# mouse.net
KiCad netlist of a schematic drawn in EAGLE
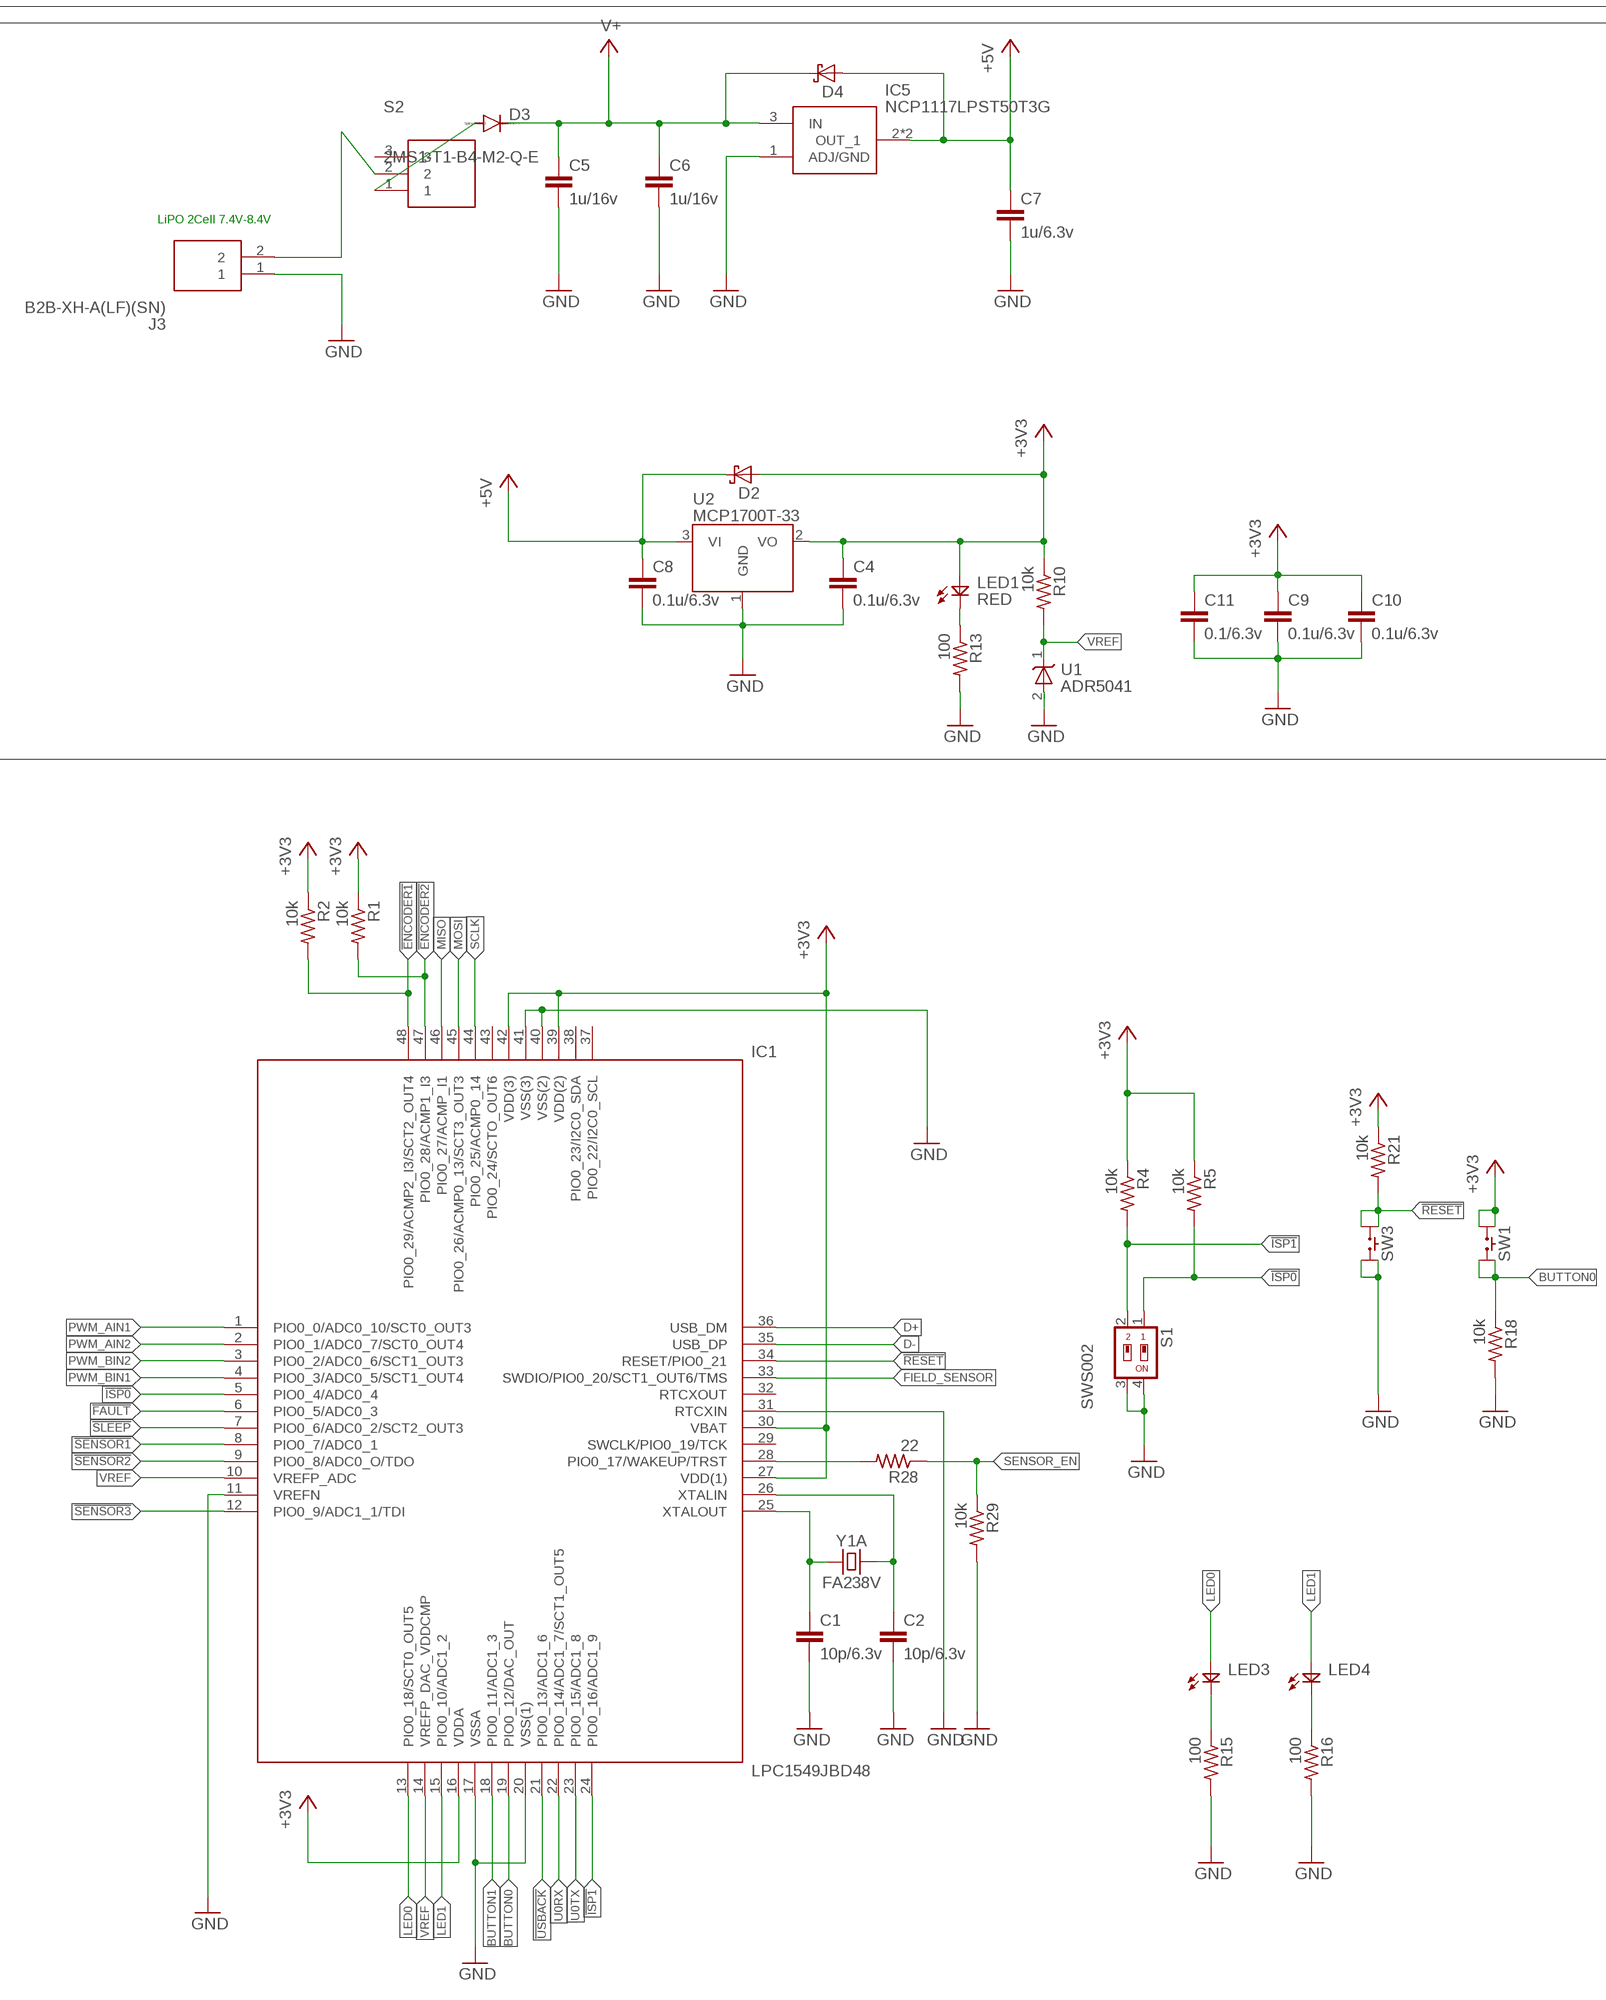
[diagram p0: schematic, sheet 1, part 1 of 2]
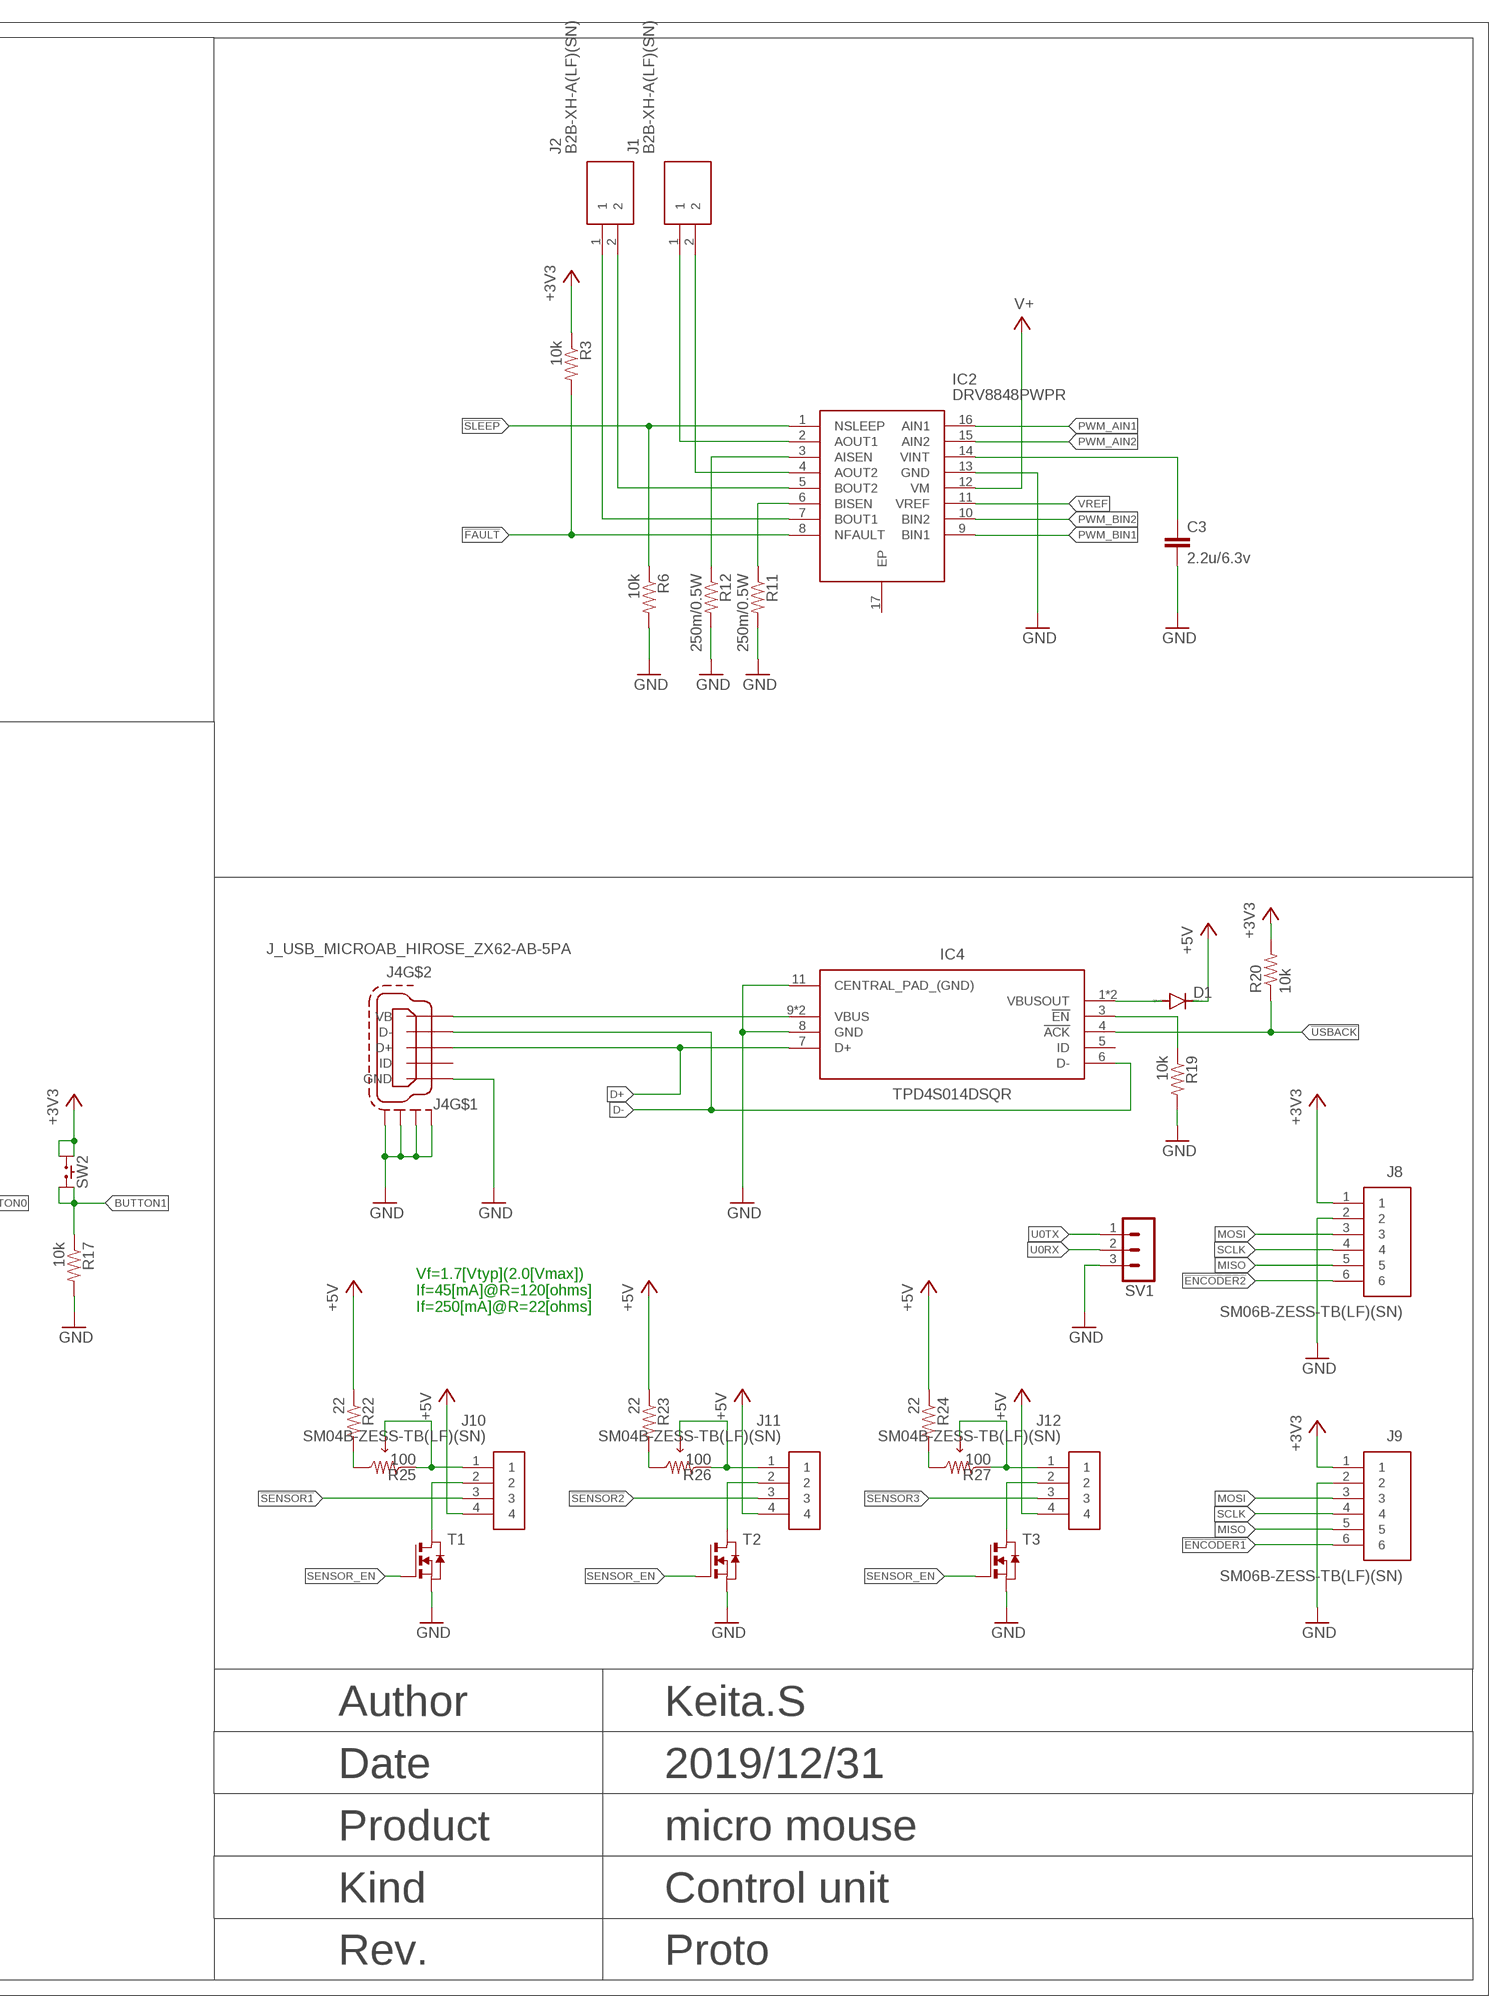
[diagram p1: schematic, sheet 1, part 2 of 2]

(export (version "E")
  (design (tool "Eeschema 10.0.6"))
  (components
    (comp (ref "C1")
      (value "10p/6.3v")
      (footprint "eagle-import:C0603")
      (libsource (lib "eagle-import") (part "C-EUC0603"))
    )
    (comp (ref "C2")
      (value "10p/6.3v")
      (footprint "eagle-import:C0603")
      (libsource (lib "eagle-import") (part "C-EUC0603"))
    )
    (comp (ref "C3")
      (value "2.2u/6.3v")
      (footprint "eagle-import:C0603")
      (libsource (lib "eagle-import") (part "C-EUC0603"))
    )
    (comp (ref "C4")
      (value "0.1u/6.3v")
      (footprint "eagle-import:C0603")
      (libsource (lib "eagle-import") (part "C-EUC0603"))
    )
    (comp (ref "C5")
      (value "1u/16v")
      (footprint "eagle-import:C0603")
      (libsource (lib "eagle-import") (part "C-EUC0603"))
    )
    (comp (ref "C6")
      (value "1u/16v")
      (footprint "eagle-import:C0603")
      (libsource (lib "eagle-import") (part "C-EUC0603"))
    )
    (comp (ref "C7")
      (value "1u/6.3v")
      (footprint "eagle-import:C0603")
      (libsource (lib "eagle-import") (part "C-EUC0603"))
    )
    (comp (ref "C8")
      (value "0.1u/6.3v")
      (footprint "eagle-import:C0603")
      (libsource (lib "eagle-import") (part "C-EUC0603"))
    )
    (comp (ref "C9")
      (value "0.1u/6.3v")
      (footprint "eagle-import:C0603")
      (libsource (lib "eagle-import") (part "C-EUC0603"))
    )
    (comp (ref "C10")
      (value "0.1u/6.3v")
      (footprint "eagle-import:C0603")
      (libsource (lib "eagle-import") (part "C-EUC0603"))
    )
    (comp (ref "C11")
      (value "0.1/6.3v")
      (footprint "eagle-import:C0603")
      (libsource (lib "eagle-import") (part "C-EUC0603"))
    )
    (comp (ref "D1")
      (value "DIODE-SMB")
      (footprint "eagle-import:SMB")
      (libsource (lib "eagle-import") (part "DIODE-SMB"))
    )
    (comp (ref "D2")
      (value "SBD-SOD523")
      (footprint "eagle-import:DIODE_SOD523")
      (libsource (lib "eagle-import") (part "SBD-SOD523"))
    )
    (comp (ref "D3")
      (value "DIODE-SMB")
      (footprint "eagle-import:SMB")
      (libsource (lib "eagle-import") (part "DIODE-SMB"))
    )
    (comp (ref "D4")
      (value "SBD-SOD523")
      (footprint "eagle-import:DIODE_SOD523")
      (libsource (lib "eagle-import") (part "SBD-SOD523"))
    )
    (comp (ref "IC1")
      (value "LPC1549JBD48")
      (footprint "eagle-import:QFP50P900X900X160-48N")
      (libsource (lib "eagle-import") (part "LPC1549JBD48"))
    )
    (comp (ref "IC2")
      (value "DRV8848PWPR")
      (footprint "eagle-import:SOP65P640X120-17N")
      (libsource (lib "eagle-import") (part "DRV8848PWPR"))
    )
    (comp (ref "IC4")
      (value "TPD4S014DSQR")
      (footprint "eagle-import:SON40P200X200X80-11N")
      (fields (field (name "RS_PART_NUMBER") "7422968"))
      (libsource (lib "eagle-import") (part "TPD4S014DSQR"))
    )
    (comp (ref "IC5")
      (value "NCP1117LPST50T3G")
      (footprint "eagle-import:SOT230P700X180-4N")
      (fields (field (name "RS_PART_NUMBER") "7857187P"))
      (libsource (lib "eagle-import") (part "NCP1117LPST50T3G"))
    )
    (comp (ref "J1")
      (value "B2B-XH-A(LF)(SN)")
      (footprint "eagle-import:SHDR2W64P0X250_1X2_740X575X700")
      (fields (field (name "RS_PART_NUMBER") "8201554P"))
      (libsource (lib "eagle-import") (part "B2B-XH-A(LF)(SN)"))
    )
    (comp (ref "J2")
      (value "B2B-XH-A(LF)(SN)")
      (footprint "eagle-import:SHDR2W64P0X250_1X2_740X575X700")
      (fields (field (name "RS_PART_NUMBER") "8201554P"))
      (libsource (lib "eagle-import") (part "B2B-XH-A(LF)(SN)"))
    )
    (comp (ref "J3")
      (value "B2B-XH-A(LF)(SN)")
      (footprint "eagle-import:SHDR2W64P0X250_1X2_740X575X700")
      (fields (field (name "RS_PART_NUMBER") "8201554P"))
      (libsource (lib "eagle-import") (part "B2B-XH-A(LF)(SN)"))
    )
    (comp (ref "J4")
      (value "J_USB_MICROAB_HIROSE_ZX62-AB-5PA")
      (footprint "eagle-import:J_USB_MICROAB_HIROSE_ZX62-AB-5PA")
      (libsource (lib "eagle-import") (part "J_USB_MICROAB_HIROSE_ZX62-AB-5PA"))
    )
    (comp (ref "J8")
      (value "SM06B-ZESS-TB(LF)(SN)")
      (footprint "eagle-import:SM06BZESSTBLFSN")
      (libsource (lib "eagle-import") (part "SM06B-ZESS-TB(LF)(SN)"))
    )
    (comp (ref "J9")
      (value "SM06B-ZESS-TB(LF)(SN)")
      (footprint "eagle-import:SM06BZESSTBLFSN")
      (libsource (lib "eagle-import") (part "SM06B-ZESS-TB(LF)(SN)"))
    )
    (comp (ref "J10")
      (value "SM04B-ZESS-TB(LF)(SN)")
      (footprint "eagle-import:SM04BZESSTBLFSN")
      (libsource (lib "eagle-import") (part "SM04B-ZESS-TB(LF)(SN)"))
    )
    (comp (ref "J11")
      (value "SM04B-ZESS-TB(LF)(SN)")
      (footprint "eagle-import:SM04BZESSTBLFSN")
      (libsource (lib "eagle-import") (part "SM04B-ZESS-TB(LF)(SN)"))
    )
    (comp (ref "J12")
      (value "SM04B-ZESS-TB(LF)(SN)")
      (footprint "eagle-import:SM04BZESSTBLFSN")
      (libsource (lib "eagle-import") (part "SM04B-ZESS-TB(LF)(SN)"))
    )
    (comp (ref "LED1")
      (value "RED")
      (footprint "eagle-import:LED1608")
      (libsource (lib "eagle-import") (part "LED1608"))
    )
    (comp (ref "LED3")
      (value "LED1608")
      (footprint "eagle-import:LED1608")
      (libsource (lib "eagle-import") (part "LED1608"))
    )
    (comp (ref "LED4")
      (value "LED1608")
      (footprint "eagle-import:LED1608")
      (libsource (lib "eagle-import") (part "LED1608"))
    )
    (comp (ref "R1")
      (value "10k")
      (footprint "eagle-import:R0603")
      (libsource (lib "eagle-import") (part "R-US_R0603"))
    )
    (comp (ref "R2")
      (value "10k")
      (footprint "eagle-import:R0603")
      (libsource (lib "eagle-import") (part "R-US_R0603"))
    )
    (comp (ref "R3")
      (value "10k")
      (footprint "eagle-import:R0603")
      (libsource (lib "eagle-import") (part "R-US_R0603"))
    )
    (comp (ref "R4")
      (value "10k")
      (footprint "eagle-import:R0603")
      (libsource (lib "eagle-import") (part "R-US_R0603"))
    )
    (comp (ref "R5")
      (value "10k")
      (footprint "eagle-import:R0603")
      (libsource (lib "eagle-import") (part "R-US_R0603"))
    )
    (comp (ref "R6")
      (value "10k")
      (footprint "eagle-import:R0603")
      (libsource (lib "eagle-import") (part "R-US_R0603"))
    )
    (comp (ref "R10")
      (value "10k")
      (footprint "eagle-import:R0603")
      (libsource (lib "eagle-import") (part "R-US_R0603"))
    )
    (comp (ref "R11")
      (value "250m/0.5W")
      (footprint "eagle-import:R1206")
      (libsource (lib "eagle-import") (part "R-US_R1206"))
    )
    (comp (ref "R12")
      (value "250m/0.5W")
      (footprint "eagle-import:R1206")
      (libsource (lib "eagle-import") (part "R-US_R1206"))
    )
    (comp (ref "R13")
      (value "100")
      (footprint "eagle-import:R0603")
      (libsource (lib "eagle-import") (part "R-US_R0603"))
    )
    (comp (ref "R15")
      (value "100")
      (footprint "eagle-import:R0603")
      (libsource (lib "eagle-import") (part "R-US_R0603"))
    )
    (comp (ref "R16")
      (value "100")
      (footprint "eagle-import:R0603")
      (libsource (lib "eagle-import") (part "R-US_R0603"))
    )
    (comp (ref "R17")
      (value "10k")
      (footprint "eagle-import:R0603")
      (libsource (lib "eagle-import") (part "R-US_R0603"))
    )
    (comp (ref "R18")
      (value "10k")
      (footprint "eagle-import:R0603")
      (libsource (lib "eagle-import") (part "R-US_R0603"))
    )
    (comp (ref "R19")
      (value "10k")
      (footprint "eagle-import:R0603")
      (libsource (lib "eagle-import") (part "R-US_R0603"))
    )
    (comp (ref "R20")
      (value "10k")
      (footprint "eagle-import:R0603")
      (libsource (lib "eagle-import") (part "R-US_R0603"))
    )
    (comp (ref "R21")
      (value "10k")
      (footprint "eagle-import:R0603")
      (libsource (lib "eagle-import") (part "R-US_R0603"))
    )
    (comp (ref "R22")
      (value "22")
      (footprint "eagle-import:R0603")
      (libsource (lib "eagle-import") (part "R-US_R0603"))
    )
    (comp (ref "R23")
      (value "22")
      (footprint "eagle-import:R0603")
      (libsource (lib "eagle-import") (part "R-US_R0603"))
    )
    (comp (ref "R24")
      (value "22")
      (footprint "eagle-import:R0603")
      (libsource (lib "eagle-import") (part "R-US_R0603"))
    )
    (comp (ref "R25")
      (value "100")
      (footprint "eagle-import:CT6EP203")
      (fields (field (name "MANUFACTURER_PART_NUMBER") "CT6EP203"))
      (libsource (lib "eagle-import") (part "CT6EP203"))
    )
    (comp (ref "R26")
      (value "100")
      (footprint "eagle-import:CT6EP203")
      (fields (field (name "MANUFACTURER_PART_NUMBER") "CT6EP203"))
      (libsource (lib "eagle-import") (part "CT6EP203"))
    )
    (comp (ref "R27")
      (value "100")
      (footprint "eagle-import:CT6EP203")
      (fields (field (name "MANUFACTURER_PART_NUMBER") "CT6EP203"))
      (libsource (lib "eagle-import") (part "CT6EP203"))
    )
    (comp (ref "R28")
      (value "22")
      (footprint "eagle-import:R0603")
      (libsource (lib "eagle-import") (part "R-US_R0603"))
    )
    (comp (ref "R29")
      (value "10k")
      (footprint "eagle-import:R0603")
      (libsource (lib "eagle-import") (part "R-US_R0603"))
    )
    (comp (ref "S1")
      (value "SWS002")
      (footprint "eagle-import:SMS-002")
      (libsource (lib "eagle-import") (part "SWS002"))
    )
    (comp (ref "S2")
      (value "2MS1-T1-B4-M2-Q-E")
      (footprint "eagle-import:2MS1-T1-B4-M2-Q-E")
      (libsource (lib "eagle-import") (part "2MS1-T1-B4-M2-Q-E"))
    )
    (comp (ref "SV1")
      (value "MA03-1")
      (footprint "eagle-import:MA03-1")
      (libsource (lib "eagle-import") (part "MA03-1"))
    )
    (comp (ref "SW1")
      (value "SKRP")
      (footprint "eagle-import:SKRP")
      (libsource (lib "eagle-import") (part "SKRP"))
    )
    (comp (ref "SW2")
      (value "SKRP")
      (footprint "eagle-import:SKRP")
      (libsource (lib "eagle-import") (part "SKRP"))
    )
    (comp (ref "SW3")
      (value "SKRP")
      (footprint "eagle-import:SKRP")
      (libsource (lib "eagle-import") (part "SKRP"))
    )
    (comp (ref "T1")
      (value "NMOSSOT23")
      (footprint "eagle-import:SOT-23")
      (libsource (lib "eagle-import") (part "NMOSSOT23"))
    )
    (comp (ref "T2")
      (value "NMOSSOT23")
      (footprint "eagle-import:SOT-23")
      (libsource (lib "eagle-import") (part "NMOSSOT23"))
    )
    (comp (ref "T3")
      (value "NMOSSOT23")
      (footprint "eagle-import:SOT-23")
      (libsource (lib "eagle-import") (part "NMOSSOT23"))
    )
    (comp (ref "U1")
      (value "ADR5041")
      (footprint "eagle-import:SC70-3")
      (libsource (lib "eagle-import") (part "ADR5041"))
    )
    (comp (ref "U2")
      (value "MCP1700T-33")
      (footprint "eagle-import:SOT23-3")
      (libsource (lib "eagle-import") (part "MCP1700T-33"))
    )
    (comp (ref "Y1")
      (value "FA238V")
      (footprint "eagle-import:EPSON_FA238V")
      (libsource (lib "eagle-import") (part "FA238V"))
    )
  )
  (nets
    (net (code "1") (name "+3V3") (class "Default")
      (node (ref "C10") (pin "1") (pinfunction "1_1") (pintype "passive"))
      (node (ref "C11") (pin "1") (pinfunction "1_1") (pintype "passive"))
      (node (ref "C4") (pin "1") (pinfunction "1_1") (pintype "passive"))
      (node (ref "C9") (pin "1") (pinfunction "1_1") (pintype "passive"))
      (node (ref "D2") (pin "A") (pinfunction "A_A") (pintype "passive"))
      (node (ref "IC1") (pin "16") (pinfunction "VDDA_16") (pintype "passive"))
      (node (ref "IC1") (pin "27") (pinfunction "VDD(1)_27") (pintype "passive"))
      (node (ref "IC1") (pin "30") (pinfunction "VBAT_30") (pintype "passive"))
      (node (ref "IC1") (pin "39") (pinfunction "VDD(2)_39") (pintype "passive"))
      (node (ref "IC1") (pin "42") (pinfunction "VDD(3)_42") (pintype "passive"))
      (node (ref "J8") (pin "1") (pinfunction "1_1") (pintype "bidirectional"))
      (node (ref "J9") (pin "1") (pinfunction "1_1") (pintype "bidirectional"))
      (node (ref "LED1") (pin "A") (pinfunction "A_A") (pintype "passive"))
      (node (ref "R1") (pin "1") (pinfunction "1_1") (pintype "passive"))
      (node (ref "R10") (pin "1") (pinfunction "1_1") (pintype "passive"))
      (node (ref "R2") (pin "1") (pinfunction "1_1") (pintype "passive"))
      (node (ref "R20") (pin "2") (pinfunction "2_2") (pintype "passive"))
      (node (ref "R21") (pin "1") (pinfunction "1_1") (pintype "passive"))
      (node (ref "R3") (pin "1") (pinfunction "1_1") (pintype "passive"))
      (node (ref "R4") (pin "1") (pinfunction "1_1") (pintype "passive"))
      (node (ref "R5") (pin "1") (pinfunction "1_1") (pintype "passive"))
      (node (ref "SW1") (pin "A1") (pinfunction "A1_A1") (pintype "passive"))
      (node (ref "SW1") (pin "A2") (pinfunction "A2_A2") (pintype "passive"))
      (node (ref "SW2") (pin "A1") (pinfunction "A1_A1") (pintype "passive"))
      (node (ref "SW2") (pin "A2") (pinfunction "A2_A2") (pintype "passive"))
      (node (ref "U2") (pin "2") (pinfunction "VO_2") (pintype "bidirectional"))
    )
    (net (code "2") (name "+5V") (class "Default")
      (node (ref "C7") (pin "1") (pinfunction "1_1") (pintype "passive"))
      (node (ref "C8") (pin "1") (pinfunction "1_1") (pintype "passive"))
      (node (ref "D1") (pin "C") (pinfunction "C_C") (pintype "passive"))
      (node (ref "D2") (pin "K") (pinfunction "K_K") (pintype "passive"))
      (node (ref "D4") (pin "A") (pinfunction "A_A") (pintype "passive"))
      (node (ref "IC5") (pin "2") (pinfunction "OUT_1_2") (pintype "output"))
      (node (ref "IC5") (pin "4") (pinfunction "OUT_1_4") (pintype "output"))
      (node (ref "J10") (pin "4") (pinfunction "4_4") (pintype "bidirectional"))
      (node (ref "J11") (pin "4") (pinfunction "4_4") (pintype "bidirectional"))
      (node (ref "J12") (pin "4") (pinfunction "4_4") (pintype "bidirectional"))
      (node (ref "R22") (pin "1") (pinfunction "1_1") (pintype "passive"))
      (node (ref "R23") (pin "1") (pinfunction "1_1") (pintype "passive"))
      (node (ref "R24") (pin "1") (pinfunction "1_1") (pintype "passive"))
      (node (ref "U2") (pin "3") (pinfunction "VI_3") (pintype "bidirectional"))
    )
    (net (code "3") (name "BUTTON0") (class "Default")
      (node (ref "IC1") (pin "19") (pinfunction "PIO0_12/DAC_OUT_19") (pintype "passive"))
      (node (ref "R18") (pin "1") (pinfunction "1_1") (pintype "passive"))
      (node (ref "SW1") (pin "B1") (pinfunction "B1_B1") (pintype "passive"))
      (node (ref "SW1") (pin "B2") (pinfunction "B2_B2") (pintype "passive"))
    )
    (net (code "4") (name "BUTTON1") (class "Default")
      (node (ref "IC1") (pin "18") (pinfunction "PIO0_11/ADC1_3_18") (pintype "passive"))
      (node (ref "R17") (pin "1") (pinfunction "1_1") (pintype "passive"))
      (node (ref "SW2") (pin "B1") (pinfunction "B1_B1") (pintype "passive"))
      (node (ref "SW2") (pin "B2") (pinfunction "B2_B2") (pintype "passive"))
    )
    (net (code "5") (name "D+") (class "Default")
      (node (ref "IC1") (pin "36") (pinfunction "USB_DM_36") (pintype "passive"))
      (node (ref "IC4") (pin "7") (pinfunction "D+_7") (pintype "passive"))
      (node (ref "J4") (pin "P$3") (pinfunction "D+_P$3") (pintype "passive"))
    )
    (net (code "6") (name "D-") (class "Default")
      (node (ref "IC1") (pin "35") (pinfunction "USB_DP_35") (pintype "passive"))
      (node (ref "IC4") (pin "6") (pinfunction "D-_6") (pintype "passive"))
      (node (ref "J4") (pin "P$2") (pinfunction "D-_P$2") (pintype "passive"))
    )
    (net (code "7") (name "FIELD_SENSOR") (class "Default")
      (node (ref "IC1") (pin "33") (pinfunction "SWDIO/PIO0_20/SCT1_OUT6/TMS_33") (pintype "passive"))
    )
    (net (code "8") (name "GND") (class "Default")
      (node (ref "C1") (pin "2") (pinfunction "2_2") (pintype "passive"))
      (node (ref "C10") (pin "2") (pinfunction "2_2") (pintype "passive"))
      (node (ref "C11") (pin "2") (pinfunction "2_2") (pintype "passive"))
      (node (ref "C2") (pin "2") (pinfunction "2_2") (pintype "passive"))
      (node (ref "C3") (pin "2") (pinfunction "2_2") (pintype "passive"))
      (node (ref "C4") (pin "2") (pinfunction "2_2") (pintype "passive"))
      (node (ref "C5") (pin "2") (pinfunction "2_2") (pintype "passive"))
      (node (ref "C6") (pin "2") (pinfunction "2_2") (pintype "passive"))
      (node (ref "C7") (pin "2") (pinfunction "2_2") (pintype "passive"))
      (node (ref "C8") (pin "2") (pinfunction "2_2") (pintype "passive"))
      (node (ref "C9") (pin "2") (pinfunction "2_2") (pintype "passive"))
      (node (ref "IC1") (pin "11") (pinfunction "VREFN_11") (pintype "passive"))
      (node (ref "IC1") (pin "17") (pinfunction "VSSA_17") (pintype "passive"))
      (node (ref "IC1") (pin "20") (pinfunction "VSS(1)_20") (pintype "passive"))
      (node (ref "IC1") (pin "31") (pinfunction "RTCXIN_31") (pintype "passive"))
      (node (ref "IC1") (pin "40") (pinfunction "VSS(2)_40") (pintype "passive"))
      (node (ref "IC1") (pin "41") (pinfunction "VSS(3)_41") (pintype "passive"))
      (node (ref "IC2") (pin "13") (pinfunction "GND_13") (pintype "bidirectional"))
      (node (ref "IC4") (pin "11") (pinfunction "CENTRAL_PAD_(GND)_11") (pintype "passive"))
      (node (ref "IC4") (pin "8") (pinfunction "GND_8") (pintype "passive"))
      (node (ref "IC5") (pin "1") (pinfunction "ADJ/GND_1") (pintype "power_in"))
      (node (ref "J3") (pin "1") (pinfunction "1_1") (pintype "bidirectional"))
      (node (ref "J4") (pin "P$5") (pinfunction "GND_P$5") (pintype "passive"))
      (node (ref "J4") (pin "SHIELD1") (pinfunction "S1_SHIELD1") (pintype "passive"))
      (node (ref "J4") (pin "SHIELD2") (pinfunction "S2_SHIELD2") (pintype "passive"))
      (node (ref "J4") (pin "SHIELD3") (pinfunction "S3_SHIELD3") (pintype "passive"))
      (node (ref "J4") (pin "SHIELD4") (pinfunction "S4_SHIELD4") (pintype "passive"))
      (node (ref "J8") (pin "2") (pinfunction "2_2") (pintype "bidirectional"))
      (node (ref "J9") (pin "2") (pinfunction "2_2") (pintype "bidirectional"))
      (node (ref "R11") (pin "2") (pinfunction "2_2") (pintype "passive"))
      (node (ref "R12") (pin "2") (pinfunction "2_2") (pintype "passive"))
      (node (ref "R13") (pin "2") (pinfunction "2_2") (pintype "passive"))
      (node (ref "R15") (pin "2") (pinfunction "2_2") (pintype "passive"))
      (node (ref "R16") (pin "2") (pinfunction "2_2") (pintype "passive"))
      (node (ref "R17") (pin "2") (pinfunction "2_2") (pintype "passive"))
      (node (ref "R18") (pin "2") (pinfunction "2_2") (pintype "passive"))
      (node (ref "R19") (pin "2") (pinfunction "2_2") (pintype "passive"))
      (node (ref "R29") (pin "2") (pinfunction "2_2") (pintype "passive"))
      (node (ref "R6") (pin "2") (pinfunction "2_2") (pintype "passive"))
      (node (ref "S1") (pin "3") (pinfunction "3_3") (pintype "passive"))
      (node (ref "S1") (pin "4") (pinfunction "4_4") (pintype "passive"))
      (node (ref "SV1") (pin "3") (pinfunction "3_3") (pintype "passive"))
      (node (ref "SW3") (pin "B1") (pinfunction "B1_B1") (pintype "passive"))
      (node (ref "SW3") (pin "B2") (pinfunction "B2_B2") (pintype "passive"))
      (node (ref "T1") (pin "2") (pinfunction "S_2") (pintype "passive"))
      (node (ref "T2") (pin "2") (pinfunction "S_2") (pintype "passive"))
      (node (ref "T3") (pin "2") (pinfunction "S_2") (pintype "passive"))
      (node (ref "U1") (pin "2") (pinfunction "A_2") (pintype "passive"))
      (node (ref "U2") (pin "1") (pinfunction "GND_1") (pintype "bidirectional"))
    )
    (net (code "9") (name "LED0") (class "Default")
      (node (ref "IC1") (pin "13") (pinfunction "PIO0_18/SCT0_OUT5_13") (pintype "passive"))
      (node (ref "LED3") (pin "A") (pinfunction "A_A") (pintype "passive"))
    )
    (net (code "10") (name "LED1") (class "Default")
      (node (ref "IC1") (pin "15") (pinfunction "PIO0_10/ADC1_2_15") (pintype "passive"))
      (node (ref "LED4") (pin "A") (pinfunction "A_A") (pintype "passive"))
    )
    (net (code "11") (name "MISO") (class "Default")
      (node (ref "IC1") (pin "46") (pinfunction "PIO0_27/ACMP_I1_46") (pintype "passive"))
      (node (ref "J8") (pin "5") (pinfunction "5_5") (pintype "bidirectional"))
      (node (ref "J9") (pin "5") (pinfunction "5_5") (pintype "bidirectional"))
    )
    (net (code "12") (name "MOSI") (class "Default")
      (node (ref "IC1") (pin "45") (pinfunction "PIO0_26/ACMP0_13/SCT3_OUT3_45") (pintype "passive"))
      (node (ref "J8") (pin "3") (pinfunction "3_3") (pintype "bidirectional"))
      (node (ref "J9") (pin "3") (pinfunction "3_3") (pintype "bidirectional"))
    )
    (net (code "13") (name "Net-(D1-PadA)") (class "Default")
      (node (ref "D1") (pin "A") (pinfunction "A_A") (pintype "passive"))
      (node (ref "IC4") (pin "1") (pinfunction "VBUSOUT_1") (pintype "passive"))
      (node (ref "IC4") (pin "2") (pinfunction "VBUSOUT_2") (pintype "passive"))
    )
    (net (code "14") (name "Net-(D3-PadA)") (class "Default")
      (node (ref "D3") (pin "A") (pinfunction "A_A") (pintype "passive"))
      (node (ref "S2") (pin "1") (pinfunction "1_1") (pintype "bidirectional"))
    )
    (net (code "15") (name "Net-(IC1-PIO0_17{slash}WAKEUP{slash}TRST)") (class "Default")
      (node (ref "IC1") (pin "28") (pinfunction "PIO0_17/WAKEUP/TRST_28") (pintype "passive"))
      (node (ref "R28") (pin "2") (pinfunction "2_2") (pintype "passive"))
    )
    (net (code "16") (name "Net-(IC1-XTALIN)") (class "Default")
      (node (ref "C2") (pin "1") (pinfunction "1_1") (pintype "passive"))
      (node (ref "IC1") (pin "26") (pinfunction "XTALIN_26") (pintype "passive"))
      (node (ref "Y1") (pin "3") (pinfunction "3_3") (pintype "passive"))
    )
    (net (code "17") (name "Net-(IC1-XTALOUT)") (class "Default")
      (node (ref "C1") (pin "1") (pinfunction "1_1") (pintype "passive"))
      (node (ref "IC1") (pin "25") (pinfunction "XTALOUT_25") (pintype "passive"))
      (node (ref "Y1") (pin "1") (pinfunction "1_1") (pintype "passive"))
    )
    (net (code "18") (name "Net-(IC2-AISEN)") (class "Default")
      (node (ref "IC2") (pin "3") (pinfunction "AISEN_3") (pintype "bidirectional"))
      (node (ref "R12") (pin "1") (pinfunction "1_1") (pintype "passive"))
    )
    (net (code "19") (name "Net-(IC2-AOUT1)") (class "Default")
      (node (ref "IC2") (pin "2") (pinfunction "AOUT1_2") (pintype "bidirectional"))
      (node (ref "J1") (pin "1") (pinfunction "1_1") (pintype "bidirectional"))
    )
    (net (code "20") (name "Net-(IC2-AOUT2)") (class "Default")
      (node (ref "IC2") (pin "4") (pinfunction "AOUT2_4") (pintype "bidirectional"))
      (node (ref "J1") (pin "2") (pinfunction "2_2") (pintype "bidirectional"))
    )
    (net (code "21") (name "Net-(IC2-BISEN)") (class "Default")
      (node (ref "IC2") (pin "6") (pinfunction "BISEN_6") (pintype "bidirectional"))
      (node (ref "R11") (pin "1") (pinfunction "1_1") (pintype "passive"))
    )
    (net (code "22") (name "Net-(IC2-BOUT1)") (class "Default")
      (node (ref "IC2") (pin "7") (pinfunction "BOUT1_7") (pintype "bidirectional"))
      (node (ref "J2") (pin "1") (pinfunction "1_1") (pintype "bidirectional"))
    )
    (net (code "23") (name "Net-(IC2-BOUT2)") (class "Default")
      (node (ref "IC2") (pin "5") (pinfunction "BOUT2_5") (pintype "bidirectional"))
      (node (ref "J2") (pin "2") (pinfunction "2_2") (pintype "bidirectional"))
    )
    (net (code "24") (name "Net-(IC2-VINT)") (class "Default")
      (node (ref "C3") (pin "1") (pinfunction "1_1") (pintype "passive"))
      (node (ref "IC2") (pin "14") (pinfunction "VINT_14") (pintype "bidirectional"))
    )
    (net (code "25") (name "Net-(IC4-~{EN})") (class "Default")
      (node (ref "IC4") (pin "3") (pinfunction "~{EN}_3") (pintype "passive"))
      (node (ref "R19") (pin "1") (pinfunction "1_1") (pintype "passive"))
    )
    (net (code "26") (name "Net-(J3-Pad2)") (class "Default")
      (node (ref "J3") (pin "2") (pinfunction "2_2") (pintype "bidirectional"))
      (node (ref "S2") (pin "2") (pinfunction "2_2") (pintype "bidirectional"))
    )
    (net (code "27") (name "Net-(J4B-VB)") (class "Default")
      (node (ref "IC4") (pin "10") (pinfunction "VBUS_10") (pintype "passive"))
      (node (ref "IC4") (pin "9") (pinfunction "VBUS_9") (pintype "passive"))
      (node (ref "J4") (pin "P$1") (pinfunction "VB_P$1") (pintype "passive"))
    )
    (net (code "28") (name "Net-(LED1-PadK)") (class "Default")
      (node (ref "LED1") (pin "K") (pinfunction "K_K") (pintype "passive"))
      (node (ref "R13") (pin "1") (pinfunction "1_1") (pintype "passive"))
    )
    (net (code "29") (name "Net-(LED3-PadK)") (class "Default")
      (node (ref "LED3") (pin "K") (pinfunction "K_K") (pintype "passive"))
      (node (ref "R15") (pin "1") (pinfunction "1_1") (pintype "passive"))
    )
    (net (code "30") (name "Net-(LED4-PadK)") (class "Default")
      (node (ref "LED4") (pin "K") (pinfunction "K_K") (pintype "passive"))
      (node (ref "R16") (pin "1") (pinfunction "1_1") (pintype "passive"))
    )
    (net (code "31") (name "Net-(R25-CCW)") (class "Default")
      (node (ref "R22") (pin "2") (pinfunction "2_2") (pintype "passive"))
      (node (ref "R25") (pin "1") (pinfunction "CCW_1") (pintype "bidirectional"))
    )
    (net (code "32") (name "Net-(R25-CW)") (class "Default")
      (node (ref "J10") (pin "1") (pinfunction "1_1") (pintype "bidirectional"))
      (node (ref "R25") (pin "2") (pinfunction "WIPER_2") (pintype "bidirectional"))
      (node (ref "R25") (pin "3") (pinfunction "CW_3") (pintype "bidirectional"))
    )
    (net (code "33") (name "Net-(R26-CCW)") (class "Default")
      (node (ref "R23") (pin "2") (pinfunction "2_2") (pintype "passive"))
      (node (ref "R26") (pin "1") (pinfunction "CCW_1") (pintype "bidirectional"))
    )
    (net (code "34") (name "Net-(R26-CW)") (class "Default")
      (node (ref "J11") (pin "1") (pinfunction "1_1") (pintype "bidirectional"))
      (node (ref "R26") (pin "2") (pinfunction "WIPER_2") (pintype "bidirectional"))
      (node (ref "R26") (pin "3") (pinfunction "CW_3") (pintype "bidirectional"))
    )
    (net (code "35") (name "Net-(R27-CCW)") (class "Default")
      (node (ref "R24") (pin "2") (pinfunction "2_2") (pintype "passive"))
      (node (ref "R27") (pin "1") (pinfunction "CCW_1") (pintype "bidirectional"))
    )
    (net (code "36") (name "Net-(R27-CW)") (class "Default")
      (node (ref "J12") (pin "1") (pinfunction "1_1") (pintype "bidirectional"))
      (node (ref "R27") (pin "2") (pinfunction "WIPER_2") (pintype "bidirectional"))
      (node (ref "R27") (pin "3") (pinfunction "CW_3") (pintype "bidirectional"))
    )
    (net (code "37") (name "Net-(T1-D)") (class "Default")
      (node (ref "J10") (pin "2") (pinfunction "2_2") (pintype "bidirectional"))
      (node (ref "T1") (pin "1") (pinfunction "D_1") (pintype "passive"))
    )
    (net (code "38") (name "Net-(T2-D)") (class "Default")
      (node (ref "J11") (pin "2") (pinfunction "2_2") (pintype "bidirectional"))
      (node (ref "T2") (pin "1") (pinfunction "D_1") (pintype "passive"))
    )
    (net (code "39") (name "Net-(T3-D)") (class "Default")
      (node (ref "J12") (pin "2") (pinfunction "2_2") (pintype "bidirectional"))
      (node (ref "T3") (pin "1") (pinfunction "D_1") (pintype "passive"))
    )
    (net (code "40") (name "PWM_AIN1") (class "Default")
      (node (ref "IC1") (pin "1") (pinfunction "PIO0_0/ADC0_10/SCT0_OUT3_1") (pintype "passive"))
      (node (ref "IC2") (pin "16") (pinfunction "AIN1_16") (pintype "bidirectional"))
    )
    (net (code "41") (name "PWM_AIN2") (class "Default")
      (node (ref "IC1") (pin "2") (pinfunction "PIO0_1/ADC0_7/SCT0_OUT4_2") (pintype "passive"))
      (node (ref "IC2") (pin "15") (pinfunction "AIN2_15") (pintype "bidirectional"))
    )
    (net (code "42") (name "PWM_BIN1") (class "Default")
      (node (ref "IC1") (pin "4") (pinfunction "PIO0_3/ADC0_5/SCT1_OUT4_4") (pintype "passive"))
      (node (ref "IC2") (pin "9") (pinfunction "BIN1_9") (pintype "bidirectional"))
    )
    (net (code "43") (name "PWM_BIN2") (class "Default")
      (node (ref "IC1") (pin "3") (pinfunction "PIO0_2/ADC0_6/SCT1_OUT3_3") (pintype "passive"))
      (node (ref "IC2") (pin "10") (pinfunction "BIN2_10") (pintype "bidirectional"))
    )
    (net (code "44") (name "SCLK") (class "Default")
      (node (ref "IC1") (pin "44") (pinfunction "PIO0_25/ACMP0_14_44") (pintype "passive"))
      (node (ref "J8") (pin "4") (pinfunction "4_4") (pintype "bidirectional"))
      (node (ref "J9") (pin "4") (pinfunction "4_4") (pintype "bidirectional"))
    )
    (net (code "45") (name "SENSOR_EN") (class "Default")
      (node (ref "R28") (pin "1") (pinfunction "1_1") (pintype "passive"))
      (node (ref "R29") (pin "1") (pinfunction "1_1") (pintype "passive"))
      (node (ref "T1") (pin "3") (pinfunction "G_3") (pintype "passive"))
      (node (ref "T2") (pin "3") (pinfunction "G_3") (pintype "passive"))
      (node (ref "T3") (pin "3") (pinfunction "G_3") (pintype "passive"))
    )
    (net (code "46") (name "U0RX") (class "Default")
      (node (ref "IC1") (pin "22") (pinfunction "PIO0_14/ADC1_7/SCT1_OUT5_22") (pintype "passive"))
      (node (ref "SV1") (pin "2") (pinfunction "2_2") (pintype "passive"))
    )
    (net (code "47") (name "U0TX") (class "Default")
      (node (ref "IC1") (pin "23") (pinfunction "PIO0_15/ADC1_8_23") (pintype "passive"))
      (node (ref "SV1") (pin "1") (pinfunction "1_1") (pintype "passive"))
    )
    (net (code "48") (name "V+") (class "Default")
      (node (ref "C5") (pin "1") (pinfunction "1_1") (pintype "passive"))
      (node (ref "C6") (pin "1") (pinfunction "1_1") (pintype "passive"))
      (node (ref "D3") (pin "C") (pinfunction "C_C") (pintype "passive"))
      (node (ref "D4") (pin "K") (pinfunction "K_K") (pintype "passive"))
      (node (ref "IC2") (pin "12") (pinfunction "VM_12") (pintype "bidirectional"))
      (node (ref "IC5") (pin "3") (pinfunction "IN_3") (pintype "input"))
    )
    (net (code "49") (name "VREF") (class "Default")
      (node (ref "IC1") (pin "10") (pinfunction "VREFP_ADC_10") (pintype "passive"))
      (node (ref "IC1") (pin "14") (pinfunction "VREFP_DAC_VDDCMP_14") (pintype "passive"))
      (node (ref "IC2") (pin "11") (pinfunction "VREF_11") (pintype "bidirectional"))
      (node (ref "R10") (pin "2") (pinfunction "2_2") (pintype "passive"))
      (node (ref "U1") (pin "1") (pinfunction "K_1") (pintype "passive"))
    )
    (net (code "50") (name "unconnected-(IC1-PIO0_22{slash}I2C0_SCL-Pad37)") (class "Default")
      (node (ref "IC1") (pin "37") (pinfunction "PIO0_22/I2C0_SCL_37") (pintype "passive"))
    )
    (net (code "51") (name "unconnected-(IC1-PIO0_23{slash}I2C0_SDA-Pad38)") (class "Default")
      (node (ref "IC1") (pin "38") (pinfunction "PIO0_23/I2C0_SDA_38") (pintype "passive"))
    )
    (net (code "52") (name "unconnected-(IC1-PIO0_24{slash}SCTO_OUT6-Pad43)") (class "Default")
      (node (ref "IC1") (pin "43") (pinfunction "PIO0_24/SCTO_OUT6_43") (pintype "passive"))
    )
    (net (code "53") (name "unconnected-(IC1-RTCXOUT-Pad32)") (class "Default")
      (node (ref "IC1") (pin "32") (pinfunction "RTCXOUT_32") (pintype "passive"))
    )
    (net (code "54") (name "unconnected-(IC1-SWCLK{slash}PIO0_19{slash}TCK-Pad29)") (class "Default")
      (node (ref "IC1") (pin "29") (pinfunction "SWCLK/PIO0_19/TCK_29") (pintype "passive"))
    )
    (net (code "55") (name "unconnected-(IC2-EP-Pad17)") (class "Default")
      (node (ref "IC2") (pin "17") (pinfunction "EP_17") (pintype "bidirectional"))
    )
    (net (code "56") (name "unconnected-(IC4-ID-Pad5)") (class "Default")
      (node (ref "IC4") (pin "5") (pinfunction "ID_5") (pintype "passive"))
    )
    (net (code "57") (name "unconnected-(J4B-ID-PadP$4)") (class "Default")
      (node (ref "J4") (pin "P$4") (pinfunction "ID_P$4") (pintype "passive"))
    )
    (net (code "58") (name "unconnected-(S2-Pad3)") (class "Default")
      (node (ref "S2") (pin "3") (pinfunction "3_3") (pintype "bidirectional"))
    )
    (net (code "59") (name "~{ENCODER1}") (class "Default")
      (node (ref "IC1") (pin "48") (pinfunction "PIO0_29/ACMP2_I3/SCT2_OUT4_48") (pintype "passive"))
      (node (ref "J9") (pin "6") (pinfunction "6_6") (pintype "bidirectional"))
      (node (ref "R2") (pin "2") (pinfunction "2_2") (pintype "passive"))
    )
    (net (code "60") (name "~{ENCODER2}") (class "Default")
      (node (ref "IC1") (pin "47") (pinfunction "PIO0_28/ACMP1_I3_47") (pintype "passive"))
      (node (ref "J8") (pin "6") (pinfunction "6_6") (pintype "bidirectional"))
      (node (ref "R1") (pin "2") (pinfunction "2_2") (pintype "passive"))
    )
    (net (code "61") (name "~{FAULT}") (class "Default")
      (node (ref "IC1") (pin "6") (pinfunction "PIO0_5/ADC0_3_6") (pintype "passive"))
      (node (ref "IC2") (pin "8") (pinfunction "NFAULT_8") (pintype "bidirectional"))
      (node (ref "R3") (pin "2") (pinfunction "2_2") (pintype "passive"))
    )
    (net (code "62") (name "~{ISP0}") (class "Default")
      (node (ref "IC1") (pin "5") (pinfunction "PIO0_4/ADC0_4_5") (pintype "passive"))
      (node (ref "R5") (pin "2") (pinfunction "2_2") (pintype "passive"))
      (node (ref "S1") (pin "1") (pinfunction "1_1") (pintype "passive"))
    )
    (net (code "63") (name "~{ISP1}") (class "Default")
      (node (ref "IC1") (pin "24") (pinfunction "PIO0_16/ADC1_9_24") (pintype "passive"))
      (node (ref "R4") (pin "2") (pinfunction "2_2") (pintype "passive"))
      (node (ref "S1") (pin "2") (pinfunction "2_2") (pintype "passive"))
    )
    (net (code "64") (name "~{RESET}") (class "Default")
      (node (ref "IC1") (pin "34") (pinfunction "RESET/PIO0_21_34") (pintype "passive"))
      (node (ref "R21") (pin "2") (pinfunction "2_2") (pintype "passive"))
      (node (ref "SW3") (pin "A1") (pinfunction "A1_A1") (pintype "passive"))
      (node (ref "SW3") (pin "A2") (pinfunction "A2_A2") (pintype "passive"))
    )
    (net (code "65") (name "~{SENSOR1}") (class "Default")
      (node (ref "IC1") (pin "8") (pinfunction "PIO0_7/ADC0_1_8") (pintype "passive"))
      (node (ref "J10") (pin "3") (pinfunction "3_3") (pintype "bidirectional"))
    )
    (net (code "66") (name "~{SENSOR2}") (class "Default")
      (node (ref "IC1") (pin "9") (pinfunction "PIO0_8/ADC0_O/TDO_9") (pintype "passive"))
      (node (ref "J11") (pin "3") (pinfunction "3_3") (pintype "bidirectional"))
    )
    (net (code "67") (name "~{SENSOR3}") (class "Default")
      (node (ref "IC1") (pin "12") (pinfunction "PIO0_9/ADC1_1/TDI_12") (pintype "passive"))
      (node (ref "J12") (pin "3") (pinfunction "3_3") (pintype "bidirectional"))
    )
    (net (code "68") (name "~{SLEEP}") (class "Default")
      (node (ref "IC1") (pin "7") (pinfunction "PIO0_6/ADC0_2/SCT2_OUT3_7") (pintype "passive"))
      (node (ref "IC2") (pin "1") (pinfunction "NSLEEP_1") (pintype "bidirectional"))
      (node (ref "R6") (pin "1") (pinfunction "1_1") (pintype "passive"))
    )
    (net (code "69") (name "~{USBACK}") (class "Default")
      (node (ref "IC1") (pin "21") (pinfunction "PIO0_13/ADC1_6_21") (pintype "passive"))
      (node (ref "IC4") (pin "4") (pinfunction "~{ACK}_4") (pintype "passive"))
      (node (ref "R20") (pin "1") (pinfunction "1_1") (pintype "passive"))
    )
  )
)
